# audio_amplifier.net
KiCad netlist of a schematic drawn in EAGLE
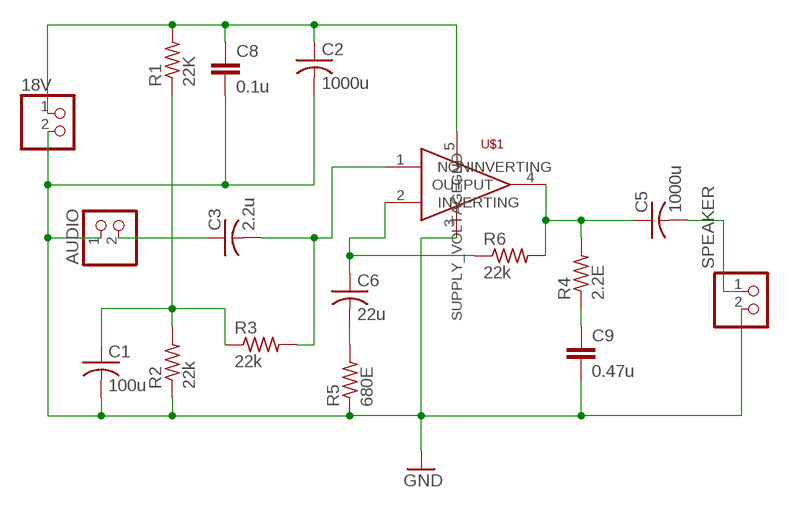
[diagram p0: schematic, sheet 1]

(export (version "E")
  (design (tool "Eeschema 10.0.6"))
  (components
    (comp (ref "18V")
      (value "PINHD-1X2")
      (footprint "eagle-import:1X02")
      (libsource (lib "eagle-import") (part "PINHD-1X2"))
    )
    (comp (ref "AUDIO")
      (value "PINHD-1X2")
      (footprint "eagle-import:1X02")
      (libsource (lib "eagle-import") (part "PINHD-1X2"))
    )
    (comp (ref "C1")
      (value "100u")
      (footprint "eagle-import:C025-024X044")
      (libsource (lib "eagle-import") (part "C-US025-024X044"))
    )
    (comp (ref "C2")
      (value "1000u")
      (footprint "eagle-import:C025-024X044")
      (libsource (lib "eagle-import") (part "C-US025-024X044"))
    )
    (comp (ref "C3")
      (value "2.2u")
      (footprint "eagle-import:C025-024X044")
      (libsource (lib "eagle-import") (part "C-US025-024X044"))
    )
    (comp (ref "C5")
      (value "1000u")
      (footprint "eagle-import:C025-024X044")
      (libsource (lib "eagle-import") (part "C-US025-024X044"))
    )
    (comp (ref "C6")
      (value "22u")
      (footprint "eagle-import:C025-024X044")
      (libsource (lib "eagle-import") (part "C-US025-024X044"))
    )
    (comp (ref "C8")
      (value "0.1u")
      (footprint "eagle-import:C025-025X050")
      (libsource (lib "eagle-import") (part "C-EU025-025X050"))
    )
    (comp (ref "C9")
      (value "0.47u")
      (footprint "eagle-import:C025-025X050")
      (libsource (lib "eagle-import") (part "C-EU025-025X050"))
    )
    (comp (ref "R1")
      (value "22K")
      (footprint "eagle-import:0204_7")
      (libsource (lib "eagle-import") (part "R-US_0204/7"))
    )
    (comp (ref "R2")
      (value "22k")
      (footprint "eagle-import:0204_7")
      (libsource (lib "eagle-import") (part "R-US_0204/7"))
    )
    (comp (ref "R3")
      (value "22k")
      (footprint "eagle-import:0204_7")
      (libsource (lib "eagle-import") (part "R-US_0204/7"))
    )
    (comp (ref "R4")
      (value "2.2E")
      (footprint "eagle-import:0204_7")
      (libsource (lib "eagle-import") (part "R-US_0204/7"))
    )
    (comp (ref "R5")
      (value "680E")
      (footprint "eagle-import:0204_7")
      (libsource (lib "eagle-import") (part "R-US_0204/7"))
    )
    (comp (ref "R6")
      (value "22k")
      (footprint "eagle-import:0204_7")
      (libsource (lib "eagle-import") (part "R-US_0204/7"))
    )
    (comp (ref "SPEAKER")
      (value "PINHD-1X2")
      (footprint "eagle-import:1X02")
      (libsource (lib "eagle-import") (part "PINHD-1X2"))
    )
    (comp (ref "U$1")
      (value "TDA2050")
      (footprint "eagle-import:PENTAWATT")
      (fields (field (name "MF") "STMicroelectronics"))
      (libsource (lib "eagle-import") (part "TDA2050"))
    )
  )
  (nets
    (net (code "1") (name "GND") (class "Default")
      (node (ref "18V") (pin "2") (pinfunction "2_2") (pintype "passive"))
      (node (ref "AUDIO") (pin "1") (pinfunction "1_1") (pintype "passive"))
      (node (ref "C1") (pin "2") (pinfunction "2_2") (pintype "passive"))
      (node (ref "C2") (pin "2") (pinfunction "2_2") (pintype "passive"))
      (node (ref "C8") (pin "2") (pinfunction "2_2") (pintype "passive"))
      (node (ref "C9") (pin "2") (pinfunction "2_2") (pintype "passive"))
      (node (ref "R2") (pin "1") (pinfunction "1_1") (pintype "passive"))
      (node (ref "R5") (pin "1") (pinfunction "1_1") (pintype "passive"))
      (node (ref "SPEAKER") (pin "2") (pinfunction "2_2") (pintype "passive"))
      (node (ref "U$1") (pin "3") (pinfunction "GND_3") (pintype "power_in"))
    )
    (net (code "2") (name "Net-(AUDIO-Pad2)") (class "Default")
      (node (ref "AUDIO") (pin "2") (pinfunction "2_2") (pintype "passive"))
      (node (ref "C3") (pin "1") (pinfunction "1_1") (pintype "passive"))
    )
    (net (code "3") (name "Net-(C1-Pad1)") (class "Default")
      (node (ref "C1") (pin "1") (pinfunction "1_1") (pintype "passive"))
      (node (ref "R1") (pin "1") (pinfunction "1_1") (pintype "passive"))
      (node (ref "R2") (pin "2") (pinfunction "2_2") (pintype "passive"))
      (node (ref "R3") (pin "1") (pinfunction "1_1") (pintype "passive"))
    )
    (net (code "4") (name "Net-(C5-Pad2)") (class "Default")
      (node (ref "C5") (pin "2") (pinfunction "2_2") (pintype "passive"))
      (node (ref "SPEAKER") (pin "1") (pinfunction "1_1") (pintype "passive"))
    )
    (net (code "5") (name "Net-(C6-Pad2)") (class "Default")
      (node (ref "C6") (pin "2") (pinfunction "2_2") (pintype "passive"))
      (node (ref "R5") (pin "2") (pinfunction "2_2") (pintype "passive"))
    )
    (net (code "6") (name "Net-(C9-Pad1)") (class "Default")
      (node (ref "C9") (pin "1") (pinfunction "1_1") (pintype "passive"))
      (node (ref "R4") (pin "1") (pinfunction "1_1") (pintype "passive"))
    )
    (net (code "7") (name "Net-(U$1-INVERTING)") (class "Default")
      (node (ref "C6") (pin "1") (pinfunction "1_1") (pintype "passive"))
      (node (ref "R6") (pin "1") (pinfunction "1_1") (pintype "passive"))
      (node (ref "U$1") (pin "2") (pinfunction "INVERTING_2") (pintype "input"))
    )
    (net (code "8") (name "Net-(U$1-NONINVERTING)") (class "Default")
      (node (ref "C3") (pin "2") (pinfunction "2_2") (pintype "passive"))
      (node (ref "R3") (pin "2") (pinfunction "2_2") (pintype "passive"))
      (node (ref "U$1") (pin "1") (pinfunction "NONINVERTING_1") (pintype "input"))
    )
    (net (code "9") (name "Net-(U$1-OUTPUT)") (class "Default")
      (node (ref "C5") (pin "1") (pinfunction "1_1") (pintype "passive"))
      (node (ref "R4") (pin "2") (pinfunction "2_2") (pintype "passive"))
      (node (ref "R6") (pin "2") (pinfunction "2_2") (pintype "passive"))
      (node (ref "U$1") (pin "4") (pinfunction "OUTPUT_4") (pintype "output"))
    )
    (net (code "10") (name "Net-(U$1-SUPPLY_VOLTAGE)") (class "Default")
      (node (ref "18V") (pin "1") (pinfunction "1_1") (pintype "passive"))
      (node (ref "C2") (pin "1") (pinfunction "1_1") (pintype "passive"))
      (node (ref "C8") (pin "1") (pinfunction "1_1") (pintype "passive"))
      (node (ref "R1") (pin "2") (pinfunction "2_2") (pintype "passive"))
      (node (ref "U$1") (pin "5") (pinfunction "SUPPLY_VOLTAGE_5") (pintype "power_in"))
    )
  )
)
